# Control.net
KiCad netlist of a schematic drawn in Altium Designer
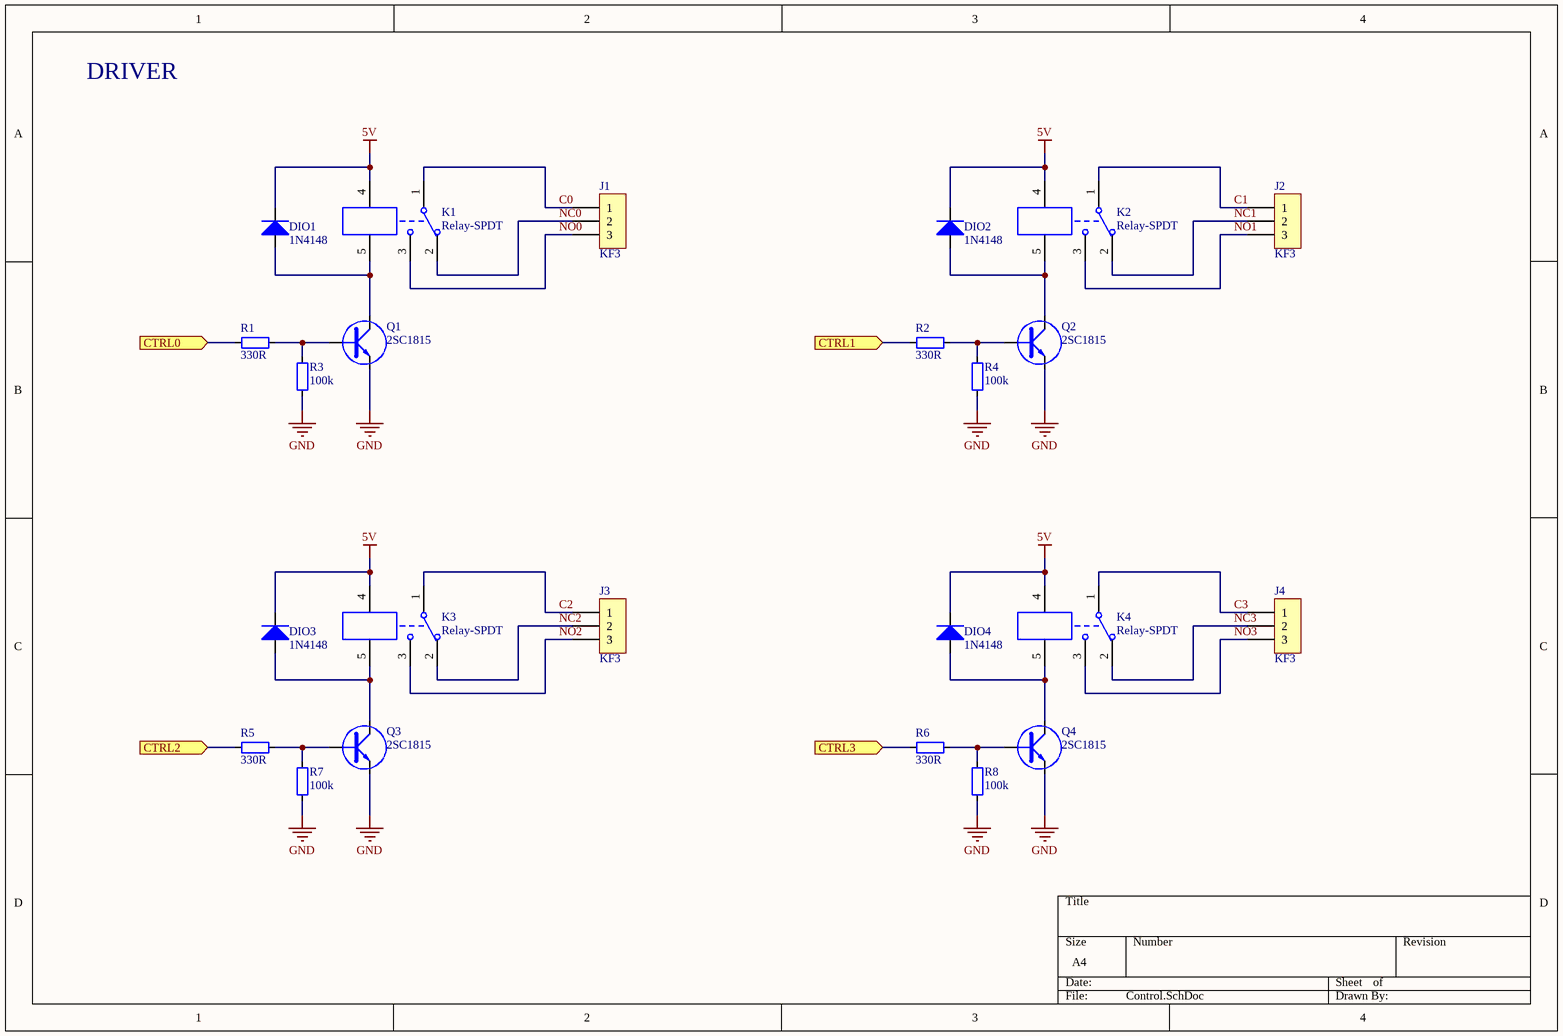
[diagram p0: Control.SchDoc]

(export (version "E")
  (design (tool "Eeschema 10.0.6"))
  (components
    (comp (ref "DIO1")
      (value "1N4148")
      (footprint "DIO-SMD-106")
      (description "Default Diode")
      (fields (field (name "PUBLISHER") "Altium Limited"))
      (libsource (lib "Ven_lib") (part "Diode SMD"))
    )
    (comp (ref "DIO2")
      (value "1N4148")
      (footprint "DIO-SMD-106")
      (description "Default Diode")
      (fields (field (name "PUBLISHER") "Altium Limited"))
      (libsource (lib "Ven_lib") (part "Diode SMD"))
    )
    (comp (ref "DIO3")
      (value "1N4148")
      (footprint "DIO-SMD-106")
      (description "Default Diode")
      (fields (field (name "PUBLISHER") "Altium Limited"))
      (libsource (lib "Ven_lib") (part "Diode SMD"))
    )
    (comp (ref "DIO4")
      (value "1N4148")
      (footprint "DIO-SMD-106")
      (description "Default Diode")
      (fields (field (name "PUBLISHER") "Altium Limited"))
      (libsource (lib "Ven_lib") (part "Diode SMD"))
    )
    (comp (ref "J1")
      (value "KF3")
      (footprint "KF3-5.08")
      (fields
        (field (name "MANUFACTURER") "Würth Elektronik eiSos GmbH")
        (field (name "PARTNO") "691103110003")
        (field (name "CREATED BY") "Karrer Zheng")
      )
      (libsource (lib "My Library") (part "KF3"))
    )
    (comp (ref "J2")
      (value "KF3")
      (footprint "KF3-5.08")
      (fields
        (field (name "MANUFACTURER") "Würth Elektronik eiSos GmbH")
        (field (name "PARTNO") "691103110003")
        (field (name "CREATED BY") "Karrer Zheng")
      )
      (libsource (lib "My Library") (part "KF3"))
    )
    (comp (ref "J3")
      (value "KF3")
      (footprint "KF3-5.08")
      (fields
        (field (name "MANUFACTURER") "Würth Elektronik eiSos GmbH")
        (field (name "PARTNO") "691103110003")
        (field (name "CREATED BY") "Karrer Zheng")
      )
      (libsource (lib "My Library") (part "KF3"))
    )
    (comp (ref "J4")
      (value "KF3")
      (footprint "KF3-5.08")
      (fields
        (field (name "MANUFACTURER") "Würth Elektronik eiSos GmbH")
        (field (name "PARTNO") "691103110003")
        (field (name "CREATED BY") "Karrer Zheng")
      )
      (libsource (lib "My Library") (part "KF3"))
    )
    (comp (ref "K1")
      (value "Relay-SPDT")
      (footprint "RELAY5PIN-10A")
      (description "Single-Pole Dual-Throw Relay")
      (fields (field (name "PUBLISHER") "Altium Limited"))
      (libsource (lib "My Library") (part "Relay-SPDT"))
    )
    (comp (ref "K2")
      (value "Relay-SPDT")
      (footprint "RELAY5PIN-10A")
      (description "Single-Pole Dual-Throw Relay")
      (fields (field (name "PUBLISHER") "Altium Limited"))
      (libsource (lib "My Library") (part "Relay-SPDT"))
    )
    (comp (ref "K3")
      (value "Relay-SPDT")
      (footprint "RELAY5PIN-10A")
      (description "Single-Pole Dual-Throw Relay")
      (fields (field (name "PUBLISHER") "Altium Limited"))
      (libsource (lib "My Library") (part "Relay-SPDT"))
    )
    (comp (ref "K4")
      (value "Relay-SPDT")
      (footprint "RELAY5PIN-10A")
      (description "Single-Pole Dual-Throw Relay")
      (fields (field (name "PUBLISHER") "Altium Limited"))
      (libsource (lib "My Library") (part "Relay-SPDT"))
    )
    (comp (ref "Q1")
      (value "2SC1815")
      (footprint "SOT23")
      (description "NPN 600mW, ECB")
      (libsource (lib "My Library") (part "2SC1815"))
    )
    (comp (ref "Q2")
      (value "2SC1815")
      (footprint "SOT23")
      (description "NPN 600mW, ECB")
      (libsource (lib "My Library") (part "2SC1815"))
    )
    (comp (ref "Q3")
      (value "2SC1815")
      (footprint "SOT23")
      (description "NPN 600mW, ECB")
      (libsource (lib "My Library") (part "2SC1815"))
    )
    (comp (ref "Q4")
      (value "2SC1815")
      (footprint "SOT23")
      (description "NPN 600mW, ECB")
      (libsource (lib "My Library") (part "2SC1815"))
    )
    (comp (ref "R1")
      (value "330R")
      (footprint "RES-SMD-0805")
      (description "Resistor")
      (fields
        (field (name "MANUFACTURER") "Generic Components")
        (field (name "PUBLISHER") "Altium Hobart Technology Centre")
      )
      (libsource (lib "My Library") (part "Resistor - SMD"))
    )
    (comp (ref "R2")
      (value "330R")
      (footprint "RES-SMD-0805")
      (description "Resistor")
      (fields
        (field (name "MANUFACTURER") "Generic Components")
        (field (name "PUBLISHER") "Altium Hobart Technology Centre")
      )
      (libsource (lib "My Library") (part "Resistor - SMD"))
    )
    (comp (ref "R3")
      (value "100k")
      (footprint "RES-SMD-0805")
      (description "Resistor")
      (fields
        (field (name "MANUFACTURER") "Generic Components")
        (field (name "PUBLISHER") "Altium Hobart Technology Centre")
      )
      (libsource (lib "My Library") (part "Resistor - SMD"))
    )
    (comp (ref "R4")
      (value "100k")
      (footprint "RES-SMD-0805")
      (description "Resistor")
      (fields
        (field (name "MANUFACTURER") "Generic Components")
        (field (name "PUBLISHER") "Altium Hobart Technology Centre")
      )
      (libsource (lib "My Library") (part "Resistor - SMD"))
    )
    (comp (ref "R5")
      (value "330R")
      (footprint "RES-SMD-0805")
      (description "Resistor")
      (fields
        (field (name "MANUFACTURER") "Generic Components")
        (field (name "PUBLISHER") "Altium Hobart Technology Centre")
      )
      (libsource (lib "My Library") (part "Resistor - SMD"))
    )
    (comp (ref "R6")
      (value "330R")
      (footprint "RES-SMD-0805")
      (description "Resistor")
      (fields
        (field (name "MANUFACTURER") "Generic Components")
        (field (name "PUBLISHER") "Altium Hobart Technology Centre")
      )
      (libsource (lib "My Library") (part "Resistor - SMD"))
    )
    (comp (ref "R7")
      (value "100k")
      (footprint "RES-SMD-0805")
      (description "Resistor")
      (fields
        (field (name "MANUFACTURER") "Generic Components")
        (field (name "PUBLISHER") "Altium Hobart Technology Centre")
      )
      (libsource (lib "My Library") (part "Resistor - SMD"))
    )
    (comp (ref "R8")
      (value "100k")
      (footprint "RES-SMD-0805")
      (description "Resistor")
      (fields
        (field (name "MANUFACTURER") "Generic Components")
        (field (name "PUBLISHER") "Altium Hobart Technology Centre")
      )
      (libsource (lib "My Library") (part "Resistor - SMD"))
    )
  )
  (nets
    (net (code "1") (name "/C0") (class "Default")
      (node (ref "J1") (pin "1") (pinfunction "1_1") (pintype "passive"))
      (node (ref "K1") (pin "1") (pinfunction "1_1") (pintype "passive"))
    )
    (net (code "2") (name "/C1") (class "Default")
      (node (ref "J2") (pin "1") (pinfunction "1_1") (pintype "passive"))
      (node (ref "K2") (pin "1") (pinfunction "1_1") (pintype "passive"))
    )
    (net (code "3") (name "/C2") (class "Default")
      (node (ref "J3") (pin "1") (pinfunction "1_1") (pintype "passive"))
      (node (ref "K3") (pin "1") (pinfunction "1_1") (pintype "passive"))
    )
    (net (code "4") (name "/C3") (class "Default")
      (node (ref "J4") (pin "1") (pinfunction "1_1") (pintype "passive"))
      (node (ref "K4") (pin "1") (pinfunction "1_1") (pintype "passive"))
    )
    (net (code "5") (name "/CTRL0") (class "Default")
      (node (ref "R1") (pin "1") (pinfunction "1_1") (pintype "passive"))
    )
    (net (code "6") (name "/CTRL1") (class "Default")
      (node (ref "R2") (pin "1") (pinfunction "1_1") (pintype "passive"))
    )
    (net (code "7") (name "/CTRL2") (class "Default")
      (node (ref "R5") (pin "1") (pinfunction "1_1") (pintype "passive"))
    )
    (net (code "8") (name "/CTRL3") (class "Default")
      (node (ref "R6") (pin "1") (pinfunction "1_1") (pintype "passive"))
    )
    (net (code "9") (name "/NC0") (class "Default")
      (node (ref "J1") (pin "2") (pinfunction "2_2") (pintype "passive"))
      (node (ref "K1") (pin "2") (pinfunction "2_2") (pintype "passive"))
    )
    (net (code "10") (name "/NC1") (class "Default")
      (node (ref "J2") (pin "2") (pinfunction "2_2") (pintype "passive"))
      (node (ref "K2") (pin "2") (pinfunction "2_2") (pintype "passive"))
    )
    (net (code "11") (name "/NC2") (class "Default")
      (node (ref "J3") (pin "2") (pinfunction "2_2") (pintype "passive"))
      (node (ref "K3") (pin "2") (pinfunction "2_2") (pintype "passive"))
    )
    (net (code "12") (name "/NC3") (class "Default")
      (node (ref "J4") (pin "2") (pinfunction "2_2") (pintype "passive"))
      (node (ref "K4") (pin "2") (pinfunction "2_2") (pintype "passive"))
    )
    (net (code "13") (name "/NO0") (class "Default")
      (node (ref "J1") (pin "3") (pinfunction "3_3") (pintype "passive"))
      (node (ref "K1") (pin "3") (pinfunction "3_3") (pintype "passive"))
    )
    (net (code "14") (name "/NO1") (class "Default")
      (node (ref "J2") (pin "3") (pinfunction "3_3") (pintype "passive"))
      (node (ref "K2") (pin "3") (pinfunction "3_3") (pintype "passive"))
    )
    (net (code "15") (name "/NO2") (class "Default")
      (node (ref "J3") (pin "3") (pinfunction "3_3") (pintype "passive"))
      (node (ref "K3") (pin "3") (pinfunction "3_3") (pintype "passive"))
    )
    (net (code "16") (name "/NO3") (class "Default")
      (node (ref "J4") (pin "3") (pinfunction "3_3") (pintype "passive"))
      (node (ref "K4") (pin "3") (pinfunction "3_3") (pintype "passive"))
    )
    (net (code "17") (name "5V") (class "Default")
      (node (ref "DIO1") (pin "2") (pinfunction "K_2") (pintype "passive"))
      (node (ref "DIO2") (pin "2") (pinfunction "K_2") (pintype "passive"))
      (node (ref "DIO3") (pin "2") (pinfunction "K_2") (pintype "passive"))
      (node (ref "DIO4") (pin "2") (pinfunction "K_2") (pintype "passive"))
      (node (ref "K1") (pin "4") (pinfunction "4_4") (pintype "passive"))
      (node (ref "K2") (pin "4") (pinfunction "4_4") (pintype "passive"))
      (node (ref "K3") (pin "4") (pinfunction "4_4") (pintype "passive"))
      (node (ref "K4") (pin "4") (pinfunction "4_4") (pintype "passive"))
    )
    (net (code "18") (name "GND") (class "Default")
      (node (ref "Q1") (pin "3") (pinfunction "E_3") (pintype "passive"))
      (node (ref "Q2") (pin "3") (pinfunction "E_3") (pintype "passive"))
      (node (ref "Q3") (pin "3") (pinfunction "E_3") (pintype "passive"))
      (node (ref "Q4") (pin "3") (pinfunction "E_3") (pintype "passive"))
      (node (ref "R3") (pin "1") (pinfunction "1_1") (pintype "passive"))
      (node (ref "R4") (pin "1") (pinfunction "1_1") (pintype "passive"))
      (node (ref "R7") (pin "1") (pinfunction "1_1") (pintype "passive"))
      (node (ref "R8") (pin "1") (pinfunction "1_1") (pintype "passive"))
    )
    (net (code "19") (name "Net-(DIO1-A)") (class "Default")
      (node (ref "DIO1") (pin "1") (pinfunction "A_1") (pintype "passive"))
      (node (ref "K1") (pin "5") (pinfunction "5_5") (pintype "passive"))
      (node (ref "Q1") (pin "2") (pinfunction "C_2") (pintype "passive"))
    )
    (net (code "20") (name "Net-(DIO2-A)") (class "Default")
      (node (ref "DIO2") (pin "1") (pinfunction "A_1") (pintype "passive"))
      (node (ref "K2") (pin "5") (pinfunction "5_5") (pintype "passive"))
      (node (ref "Q2") (pin "2") (pinfunction "C_2") (pintype "passive"))
    )
    (net (code "21") (name "Net-(DIO3-A)") (class "Default")
      (node (ref "DIO3") (pin "1") (pinfunction "A_1") (pintype "passive"))
      (node (ref "K3") (pin "5") (pinfunction "5_5") (pintype "passive"))
      (node (ref "Q3") (pin "2") (pinfunction "C_2") (pintype "passive"))
    )
    (net (code "22") (name "Net-(DIO4-A)") (class "Default")
      (node (ref "DIO4") (pin "1") (pinfunction "A_1") (pintype "passive"))
      (node (ref "K4") (pin "5") (pinfunction "5_5") (pintype "passive"))
      (node (ref "Q4") (pin "2") (pinfunction "C_2") (pintype "passive"))
    )
    (net (code "23") (name "Net-(Q1-B)") (class "Default")
      (node (ref "Q1") (pin "1") (pinfunction "B_1") (pintype "passive"))
      (node (ref "R1") (pin "2") (pinfunction "2_2") (pintype "passive"))
      (node (ref "R3") (pin "2") (pinfunction "2_2") (pintype "passive"))
    )
    (net (code "24") (name "Net-(Q2-B)") (class "Default")
      (node (ref "Q2") (pin "1") (pinfunction "B_1") (pintype "passive"))
      (node (ref "R2") (pin "2") (pinfunction "2_2") (pintype "passive"))
      (node (ref "R4") (pin "2") (pinfunction "2_2") (pintype "passive"))
    )
    (net (code "25") (name "Net-(Q3-B)") (class "Default")
      (node (ref "Q3") (pin "1") (pinfunction "B_1") (pintype "passive"))
      (node (ref "R5") (pin "2") (pinfunction "2_2") (pintype "passive"))
      (node (ref "R7") (pin "2") (pinfunction "2_2") (pintype "passive"))
    )
    (net (code "26") (name "Net-(Q4-B)") (class "Default")
      (node (ref "Q4") (pin "1") (pinfunction "B_1") (pintype "passive"))
      (node (ref "R6") (pin "2") (pinfunction "2_2") (pintype "passive"))
      (node (ref "R8") (pin "2") (pinfunction "2_2") (pintype "passive"))
    )
  )
)
